# 04_LMS7002M_Misc.net
KiCad netlist of a schematic drawn in Altium Designer
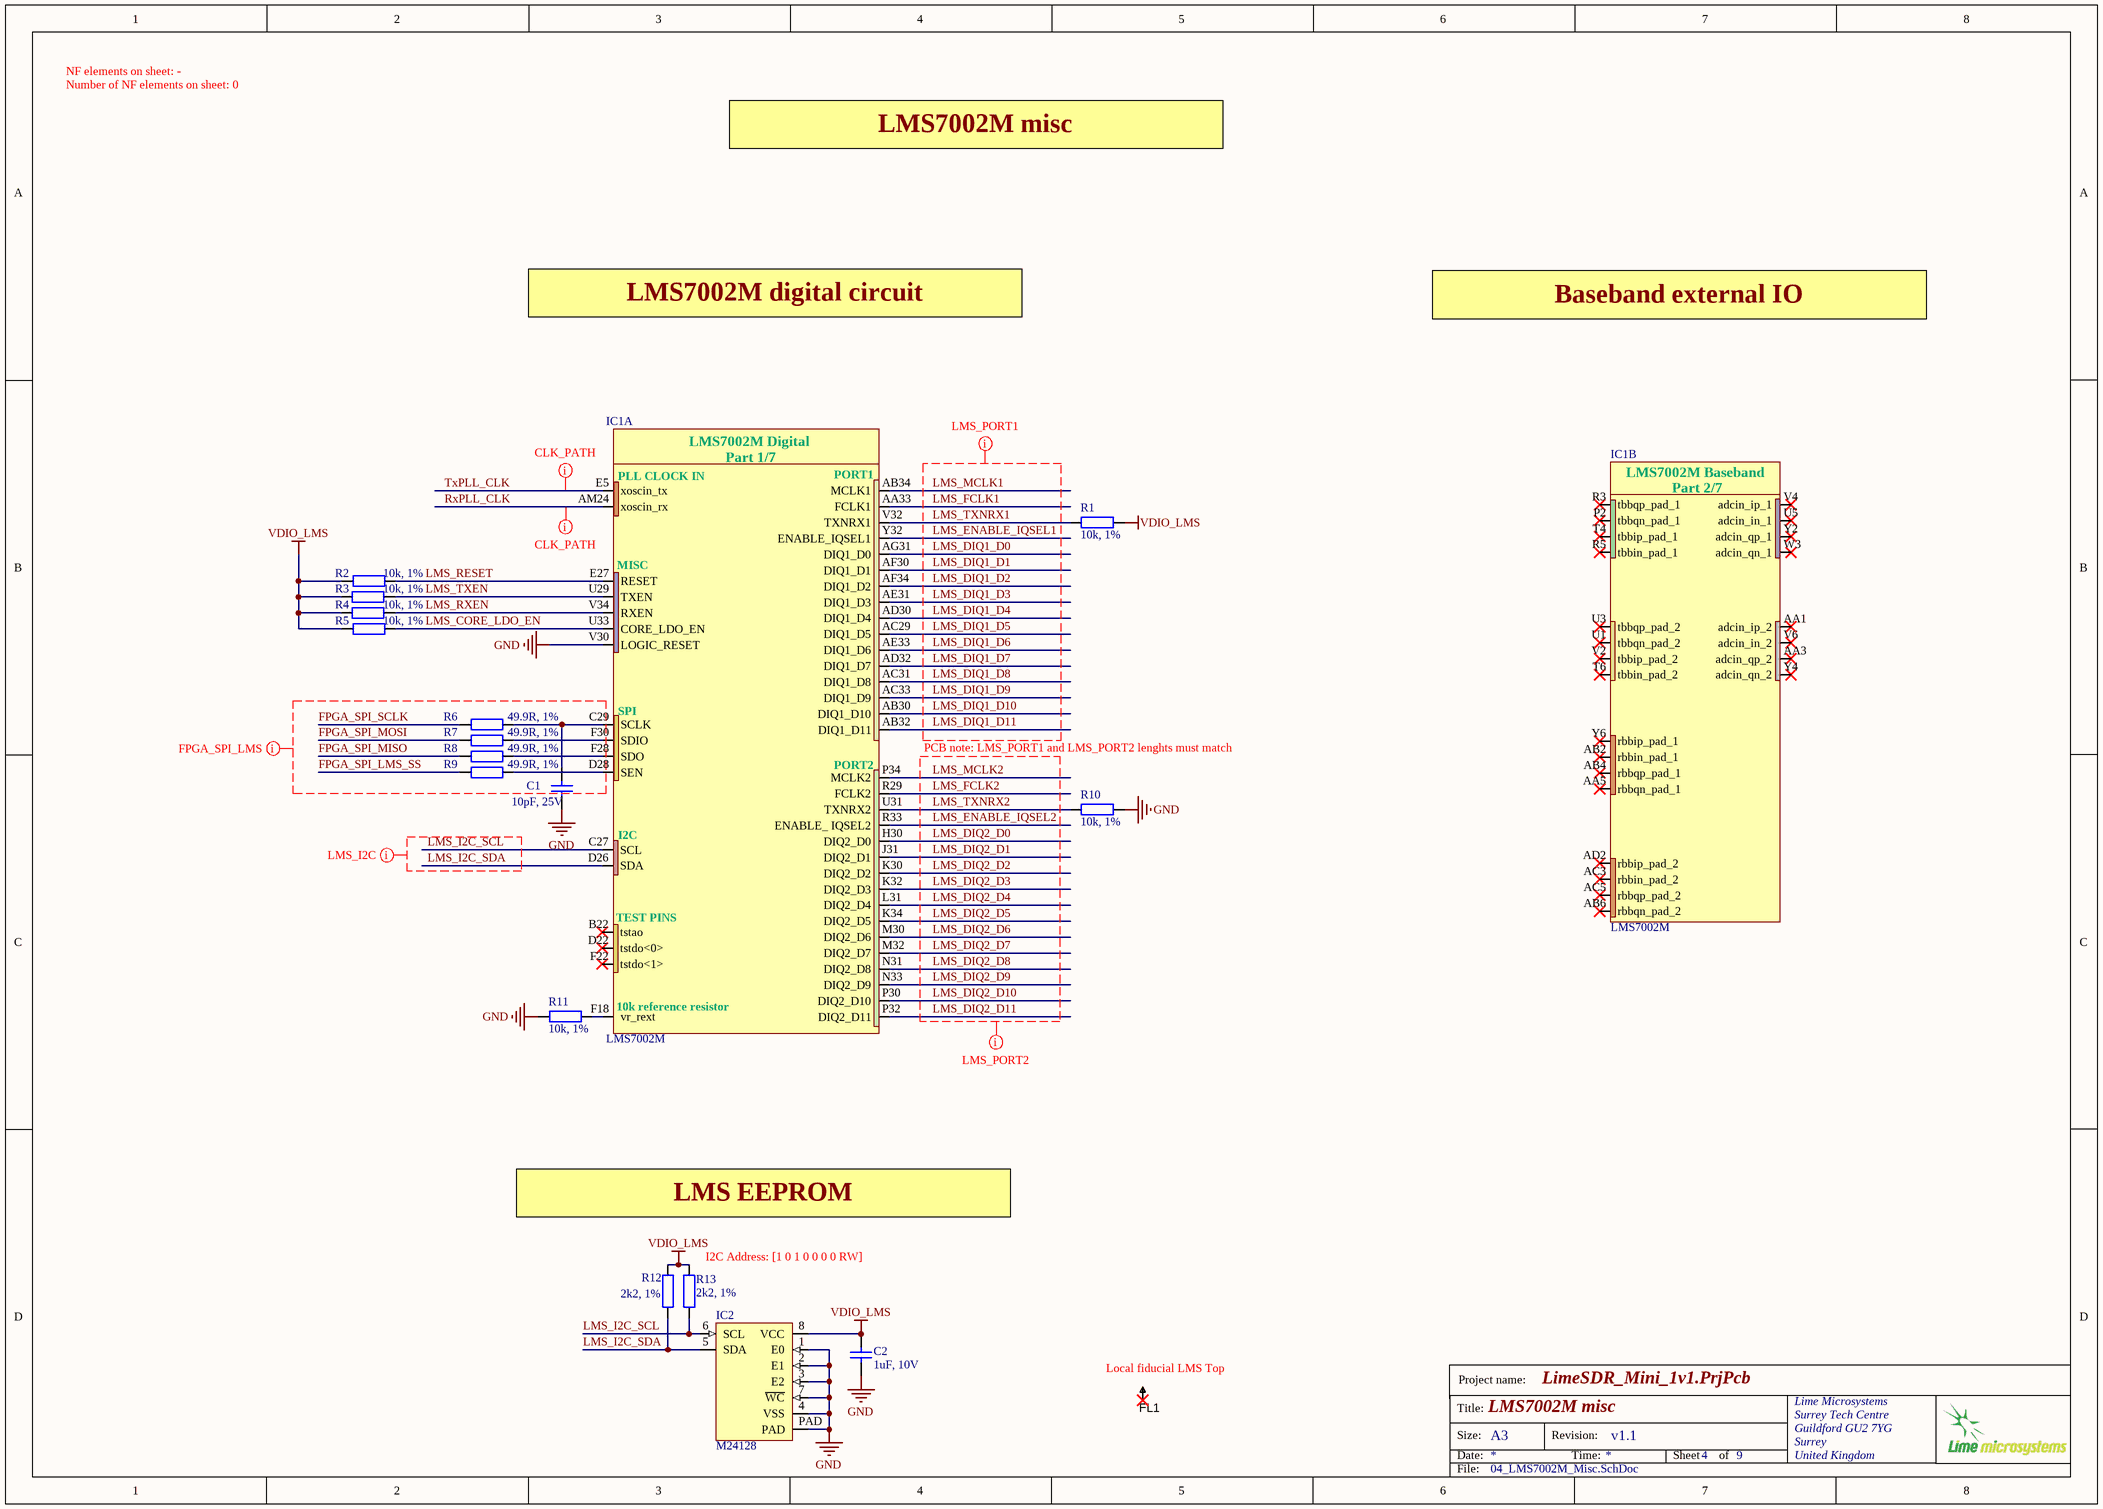
[diagram p0: 04_LMS7002M_Misc.SchDoc]

(export (version "E")
  (design (tool "Eeschema 10.0.6"))
  (components
    (comp (ref "C1")
      (value "10pF, 25V")
      (footprint "CAP0402")
      (fields (field (name "MANUFACTURER") "AVX"))
      (libsource (lib "LimeMicroAltiumLib_schLib") (part "Cap_0402"))
    )
    (comp (ref "C2")
      (value "1uF, 10V")
      (footprint "CAP0402")
      (fields (field (name "MANUFACTURER") "TDK"))
      (libsource (lib "LimeMicroAltiumLib_schLib") (part "Cap_0402"))
    )
    (comp (ref "FL1")
      (value "Fiducial")
      (footprint "Fiducial_local")
      (libsource (lib "VGTU_Altium_lib") (part "Fiducial"))
    )
    (comp (ref "IC1")
      (value "LMS7002M")
      (footprint "LMS7002M_v5_1")
      (description "Schematic symbol revision 3. Default footprint - 0.31mm pad")
      (fields (field (name "MANUFACTURER") "Lime Microsystems"))
      (libsource (lib "LimeMicroAltiumLib_schLib") (part "LMS7002Mr3"))
    )
    (comp (ref "IC2")
      (value "M24128")
      (footprint "M24128-DFMC6TG")
      (fields (field (name "MANUFACTURER") "STMicroelectronics"))
      (libsource (lib "LimeMicroAltiumLib_schLib") (part "M24128-DFMC6TG"))
    )
    (comp (ref "R1")
      (value "10k, 1%")
      (footprint "RES0402")
      (fields (field (name "MANUFACTURER") "Yageo") (field (name "TOLERANCE") "±1%"))
      (libsource (lib "LimeMicroAltiumLib_schLib") (part "Res_0402"))
    )
    (comp (ref "R2")
      (value "10k, 1%")
      (footprint "RES0402")
      (fields (field (name "MANUFACTURER") "Yageo") (field (name "TOLERANCE") "±1%"))
      (libsource (lib "LimeMicroAltiumLib_schLib") (part "Res_0402"))
    )
    (comp (ref "R3")
      (value "10k, 1%")
      (footprint "RES0402")
      (fields (field (name "MANUFACTURER") "Yageo") (field (name "TOLERANCE") "±1%"))
      (libsource (lib "LimeMicroAltiumLib_schLib") (part "Res_0402"))
    )
    (comp (ref "R4")
      (value "10k, 1%")
      (footprint "RES0402")
      (fields (field (name "MANUFACTURER") "Yageo") (field (name "TOLERANCE") "±1%"))
      (libsource (lib "LimeMicroAltiumLib_schLib") (part "Res_0402"))
    )
    (comp (ref "R5")
      (value "10k, 1%")
      (footprint "RES0402")
      (fields (field (name "MANUFACTURER") "Yageo") (field (name "TOLERANCE") "±1%"))
      (libsource (lib "LimeMicroAltiumLib_schLib") (part "Res_0402"))
    )
    (comp (ref "R6")
      (value "49.9R, 1%")
      (footprint "RES0402")
      (fields
        (field (name "TOLERANCE") "±1%")
        (field (name "MANUFACTURER") "Samsung Electro-Mechanics America, Inc.")
        (field (name "MANUFACTURER PART NUMBER") "RC1005F49R9CS")
      )
      (libsource (lib "LimeMicroAltiumLib_schLib") (part "Res_0402"))
    )
    (comp (ref "R7")
      (value "49.9R, 1%")
      (footprint "RES0402")
      (fields
        (field (name "TOLERANCE") "±1%")
        (field (name "MANUFACTURER") "Samsung Electro-Mechanics America, Inc.")
        (field (name "MANUFACTURER PART NUMBER") "RC1005F49R9CS")
      )
      (libsource (lib "LimeMicroAltiumLib_schLib") (part "Res_0402"))
    )
    (comp (ref "R8")
      (value "49.9R, 1%")
      (footprint "RES0402")
      (fields
        (field (name "TOLERANCE") "±1%")
        (field (name "MANUFACTURER") "Samsung Electro-Mechanics America, Inc.")
        (field (name "MANUFACTURER PART NUMBER") "RC1005F49R9CS")
      )
      (libsource (lib "LimeMicroAltiumLib_schLib") (part "Res_0402"))
    )
    (comp (ref "R9")
      (value "49.9R, 1%")
      (footprint "RES0402")
      (fields
        (field (name "TOLERANCE") "±1%")
        (field (name "MANUFACTURER") "Samsung Electro-Mechanics America, Inc.")
        (field (name "MANUFACTURER PART NUMBER") "RC1005F49R9CS")
      )
      (libsource (lib "LimeMicroAltiumLib_schLib") (part "Res_0402"))
    )
    (comp (ref "R10")
      (value "10k, 1%")
      (footprint "RES0402")
      (fields (field (name "MANUFACTURER") "Yageo") (field (name "TOLERANCE") "±1%"))
      (libsource (lib "LimeMicroAltiumLib_schLib") (part "Res_0402"))
    )
    (comp (ref "R11")
      (value "10k, 1%")
      (footprint "RES0402")
      (fields (field (name "MANUFACTURER") "Yageo") (field (name "TOLERANCE") "±1%"))
      (libsource (lib "LimeMicroAltiumLib_schLib") (part "Res_0402"))
    )
    (comp (ref "R12")
      (value "2k2, 1%")
      (footprint "RES0402")
      (fields (field (name "MANUFACTURER") "Stackpole Electronics Inc") (field (name "TOLERANCE") "±1%"))
      (libsource (lib "LimeMicroAltiumLib_schLib") (part "Res_0402"))
    )
    (comp (ref "R13")
      (value "2k2, 1%")
      (footprint "RES0402")
      (fields (field (name "MANUFACTURER") "Stackpole Electronics Inc") (field (name "TOLERANCE") "±1%"))
      (libsource (lib "LimeMicroAltiumLib_schLib") (part "Res_0402"))
    )
  )
  (nets
    (net (code "1") (name "/FPGA_SPI_LMS_SS") (class "Default")
      (node (ref "R9") (pin "2") (pinfunction "2_2") (pintype "passive"))
    )
    (net (code "2") (name "/FPGA_SPI_MISO") (class "Default")
      (node (ref "R8") (pin "2") (pinfunction "2_2") (pintype "passive"))
    )
    (net (code "3") (name "/FPGA_SPI_MOSI") (class "Default")
      (node (ref "R7") (pin "2") (pinfunction "2_2") (pintype "passive"))
    )
    (net (code "4") (name "/FPGA_SPI_SCLK") (class "Default")
      (node (ref "R6") (pin "2") (pinfunction "2_2") (pintype "passive"))
    )
    (net (code "5") (name "/LMS_CORE_LDO_EN") (class "Default")
      (node (ref "IC1") (pin "U33") (pinfunction "CORE_LDO_EN_U33") (pintype "passive"))
      (node (ref "R5") (pin "1") (pinfunction "1_1") (pintype "passive"))
    )
    (net (code "6") (name "/LMS_DIQ1_D0") (class "Default")
      (node (ref "IC1") (pin "AG31") (pinfunction "DIQ1_D0_AG31") (pintype "passive"))
    )
    (net (code "7") (name "/LMS_DIQ1_D1") (class "Default")
      (node (ref "IC1") (pin "AF30") (pinfunction "DIQ1_D1_AF30") (pintype "passive"))
    )
    (net (code "8") (name "/LMS_DIQ1_D2") (class "Default")
      (node (ref "IC1") (pin "AF34") (pinfunction "DIQ1_D2_AF34") (pintype "passive"))
    )
    (net (code "9") (name "/LMS_DIQ1_D3") (class "Default")
      (node (ref "IC1") (pin "AE31") (pinfunction "DIQ1_D3_AE31") (pintype "passive"))
    )
    (net (code "10") (name "/LMS_DIQ1_D4") (class "Default")
      (node (ref "IC1") (pin "AD30") (pinfunction "DIQ1_D4_AD30") (pintype "passive"))
    )
    (net (code "11") (name "/LMS_DIQ1_D5") (class "Default")
      (node (ref "IC1") (pin "AC29") (pinfunction "DIQ1_D5_AC29") (pintype "passive"))
    )
    (net (code "12") (name "/LMS_DIQ1_D6") (class "Default")
      (node (ref "IC1") (pin "AE33") (pinfunction "DIQ1_D6_AE33") (pintype "passive"))
    )
    (net (code "13") (name "/LMS_DIQ1_D7") (class "Default")
      (node (ref "IC1") (pin "AD32") (pinfunction "DIQ1_D7_AD32") (pintype "passive"))
    )
    (net (code "14") (name "/LMS_DIQ1_D8") (class "Default")
      (node (ref "IC1") (pin "AC31") (pinfunction "DIQ1_D8_AC31") (pintype "passive"))
    )
    (net (code "15") (name "/LMS_DIQ1_D9") (class "Default")
      (node (ref "IC1") (pin "AC33") (pinfunction "DIQ1_D9_AC33") (pintype "passive"))
    )
    (net (code "16") (name "/LMS_DIQ1_D10") (class "Default")
      (node (ref "IC1") (pin "AB30") (pinfunction "DIQ1_D10_AB30") (pintype "passive"))
    )
    (net (code "17") (name "/LMS_DIQ1_D11") (class "Default")
      (node (ref "IC1") (pin "AB32") (pinfunction "DIQ1_D11_AB32") (pintype "passive"))
    )
    (net (code "18") (name "/LMS_DIQ2_D0") (class "Default")
      (node (ref "IC1") (pin "H30") (pinfunction "DIQ2_D0_H30") (pintype "passive"))
    )
    (net (code "19") (name "/LMS_DIQ2_D1") (class "Default")
      (node (ref "IC1") (pin "J31") (pinfunction "DIQ2_D1_J31") (pintype "passive"))
    )
    (net (code "20") (name "/LMS_DIQ2_D2") (class "Default")
      (node (ref "IC1") (pin "K30") (pinfunction "DIQ2_D2_K30") (pintype "passive"))
    )
    (net (code "21") (name "/LMS_DIQ2_D3") (class "Default")
      (node (ref "IC1") (pin "K32") (pinfunction "DIQ2_D3_K32") (pintype "passive"))
    )
    (net (code "22") (name "/LMS_DIQ2_D4") (class "Default")
      (node (ref "IC1") (pin "L31") (pinfunction "DIQ2_D4_L31") (pintype "passive"))
    )
    (net (code "23") (name "/LMS_DIQ2_D5") (class "Default")
      (node (ref "IC1") (pin "K34") (pinfunction "DIQ2_D5_K34") (pintype "passive"))
    )
    (net (code "24") (name "/LMS_DIQ2_D6") (class "Default")
      (node (ref "IC1") (pin "M30") (pinfunction "DIQ2_D6_M30") (pintype "passive"))
    )
    (net (code "25") (name "/LMS_DIQ2_D7") (class "Default")
      (node (ref "IC1") (pin "M32") (pinfunction "DIQ2_D7_M32") (pintype "passive"))
    )
    (net (code "26") (name "/LMS_DIQ2_D8") (class "Default")
      (node (ref "IC1") (pin "N31") (pinfunction "DIQ2_D8_N31") (pintype "passive"))
    )
    (net (code "27") (name "/LMS_DIQ2_D9") (class "Default")
      (node (ref "IC1") (pin "N33") (pinfunction "DIQ2_D9_N33") (pintype "passive"))
    )
    (net (code "28") (name "/LMS_DIQ2_D10") (class "Default")
      (node (ref "IC1") (pin "P30") (pinfunction "DIQ2_D10_P30") (pintype "passive"))
    )
    (net (code "29") (name "/LMS_DIQ2_D11") (class "Default")
      (node (ref "IC1") (pin "P32") (pinfunction "DIQ2_D11_P32") (pintype "passive"))
    )
    (net (code "30") (name "/LMS_ENABLE_IQSEL1") (class "Default")
      (node (ref "IC1") (pin "Y32") (pinfunction "ENABLE_IQSEL1_Y32") (pintype "passive"))
    )
    (net (code "31") (name "/LMS_ENABLE_IQSEL2") (class "Default")
      (node (ref "IC1") (pin "R33") (pinfunction "ENABLE__IQSEL2_R33") (pintype "passive"))
    )
    (net (code "32") (name "/LMS_FCLK1") (class "Default")
      (node (ref "IC1") (pin "AA33") (pinfunction "FCLK1_AA33") (pintype "passive"))
    )
    (net (code "33") (name "/LMS_FCLK2") (class "Default")
      (node (ref "IC1") (pin "R29") (pinfunction "FCLK2_R29") (pintype "passive"))
    )
    (net (code "34") (name "/LMS_I2C_SCL") (class "Default")
      (node (ref "IC1") (pin "C27") (pinfunction "SCL_C27") (pintype "passive"))
      (node (ref "IC2") (pin "6") (pinfunction "SCL_6") (pintype "input"))
      (node (ref "R13") (pin "2") (pinfunction "2_2") (pintype "passive"))
    )
    (net (code "35") (name "/LMS_I2C_SDA") (class "Default")
      (node (ref "IC1") (pin "D26") (pinfunction "SDA_D26") (pintype "passive"))
      (node (ref "IC2") (pin "5") (pinfunction "SDA_5") (pintype "bidirectional"))
      (node (ref "R12") (pin "2") (pinfunction "2_2") (pintype "passive"))
    )
    (net (code "36") (name "/LMS_MCLK1") (class "Default")
      (node (ref "IC1") (pin "AB34") (pinfunction "MCLK1_AB34") (pintype "passive"))
    )
    (net (code "37") (name "/LMS_MCLK2") (class "Default")
      (node (ref "IC1") (pin "P34") (pinfunction "MCLK2_P34") (pintype "passive"))
    )
    (net (code "38") (name "/LMS_RESET") (class "Default")
      (node (ref "IC1") (pin "E27") (pinfunction "RESET_E27") (pintype "passive"))
      (node (ref "R2") (pin "1") (pinfunction "1_1") (pintype "passive"))
    )
    (net (code "39") (name "/LMS_RXEN") (class "Default")
      (node (ref "IC1") (pin "V34") (pinfunction "RXEN_V34") (pintype "passive"))
      (node (ref "R4") (pin "2") (pinfunction "2_2") (pintype "passive"))
    )
    (net (code "40") (name "/LMS_TXEN") (class "Default")
      (node (ref "IC1") (pin "U29") (pinfunction "TXEN_U29") (pintype "passive"))
      (node (ref "R3") (pin "2") (pinfunction "2_2") (pintype "passive"))
    )
    (net (code "41") (name "/LMS_TXNRX1") (class "Default")
      (node (ref "IC1") (pin "V32") (pinfunction "TXNRX1_V32") (pintype "passive"))
      (node (ref "R1") (pin "1") (pinfunction "1_1") (pintype "passive"))
    )
    (net (code "42") (name "/LMS_TXNRX2") (class "Default")
      (node (ref "IC1") (pin "U31") (pinfunction "TXNRX2_U31") (pintype "passive"))
      (node (ref "R10") (pin "1") (pinfunction "1_1") (pintype "passive"))
    )
    (net (code "43") (name "/RxPLL_CLK") (class "Default")
      (node (ref "IC1") (pin "AM24") (pinfunction "xoscin_rx_AM24") (pintype "passive"))
    )
    (net (code "44") (name "/TxPLL_CLK") (class "Default")
      (node (ref "IC1") (pin "E5") (pinfunction "xoscin_tx_E5") (pintype "passive"))
    )
    (net (code "45") (name "GND") (class "Default")
      (node (ref "C1") (pin "2") (pinfunction "2_2") (pintype "passive"))
      (node (ref "C2") (pin "2") (pinfunction "2_2") (pintype "passive"))
      (node (ref "IC1") (pin "V30") (pinfunction "LOGIC_RESET_V30") (pintype "passive"))
      (node (ref "IC2") (pin "1") (pinfunction "E0_1") (pintype "input"))
      (node (ref "IC2") (pin "2") (pinfunction "E1_2") (pintype "input"))
      (node (ref "IC2") (pin "3") (pinfunction "E2_3") (pintype "input"))
      (node (ref "IC2") (pin "4") (pinfunction "VSS_4") (pintype "power_in"))
      (node (ref "IC2") (pin "7") (pinfunction "~{WC}_7") (pintype "input"))
      (node (ref "IC2") (pin "PAD") (pinfunction "PAD_PAD") (pintype "power_in"))
      (node (ref "R10") (pin "2") (pinfunction "2_2") (pintype "passive"))
      (node (ref "R11") (pin "2") (pinfunction "2_2") (pintype "passive"))
    )
    (net (code "46") (name "Net-(IC1A-SCLK)") (class "Default")
      (node (ref "C1") (pin "1") (pinfunction "1_1") (pintype "passive"))
      (node (ref "IC1") (pin "C29") (pinfunction "SCLK_C29") (pintype "passive"))
      (node (ref "R6") (pin "1") (pinfunction "1_1") (pintype "passive"))
    )
    (net (code "47") (name "Net-(IC1A-SDIO)") (class "Default")
      (node (ref "IC1") (pin "F30") (pinfunction "SDIO_F30") (pintype "passive"))
      (node (ref "R7") (pin "1") (pinfunction "1_1") (pintype "passive"))
    )
    (net (code "48") (name "Net-(IC1A-SDO)") (class "Default")
      (node (ref "IC1") (pin "F28") (pinfunction "SDO_F28") (pintype "passive"))
      (node (ref "R8") (pin "1") (pinfunction "1_1") (pintype "passive"))
    )
    (net (code "49") (name "Net-(IC1A-SEN)") (class "Default")
      (node (ref "IC1") (pin "D28") (pinfunction "SEN_D28") (pintype "passive"))
      (node (ref "R9") (pin "1") (pinfunction "1_1") (pintype "passive"))
    )
    (net (code "50") (name "Net-(IC1A-vr_rext)") (class "Default")
      (node (ref "IC1") (pin "F18") (pinfunction "vr_rext_F18") (pintype "passive"))
      (node (ref "R11") (pin "1") (pinfunction "1_1") (pintype "passive"))
    )
    (net (code "51") (name "VDIO_LMS") (class "Default")
      (node (ref "C2") (pin "1") (pinfunction "1_1") (pintype "passive"))
      (node (ref "IC2") (pin "8") (pinfunction "VCC_8") (pintype "power_in"))
      (node (ref "R1") (pin "2") (pinfunction "2_2") (pintype "passive"))
      (node (ref "R12") (pin "1") (pinfunction "1_1") (pintype "passive"))
      (node (ref "R13") (pin "1") (pinfunction "1_1") (pintype "passive"))
      (node (ref "R2") (pin "2") (pinfunction "2_2") (pintype "passive"))
      (node (ref "R3") (pin "1") (pinfunction "1_1") (pintype "passive"))
      (node (ref "R4") (pin "1") (pinfunction "1_1") (pintype "passive"))
      (node (ref "R5") (pin "2") (pinfunction "2_2") (pintype "passive"))
    )
    (net (code "52") (name "unconnected-(FL1-Pad1)") (class "Default")
      (node (ref "FL1") (pin "1") (pintype "passive+no_connect"))
    )
    (net (code "53") (name "unconnected-(IC1A-tstao-PadB22)") (class "Default")
      (node (ref "IC1") (pin "B22") (pinfunction "tstao_B22") (pintype "passive+no_connect"))
    )
    (net (code "54") (name "unconnected-(IC1A-tstdo<0>-PadD22)") (class "Default")
      (node (ref "IC1") (pin "D22") (pinfunction "tstdo<0>_D22") (pintype "passive+no_connect"))
    )
    (net (code "55") (name "unconnected-(IC1A-tstdo<1>-PadF22)") (class "Default")
      (node (ref "IC1") (pin "F22") (pinfunction "tstdo<1>_F22") (pintype "passive+no_connect"))
    )
    (net (code "56") (name "unconnected-(IC1B-adcin_in_1-PadU5)") (class "Default")
      (node (ref "IC1") (pin "U5") (pinfunction "adcin_in_1_U5") (pintype "passive+no_connect"))
    )
    (net (code "57") (name "unconnected-(IC1B-adcin_in_2-PadV6)") (class "Default")
      (node (ref "IC1") (pin "V6") (pinfunction "adcin_in_2_V6") (pintype "passive+no_connect"))
    )
    (net (code "58") (name "unconnected-(IC1B-adcin_ip_1-PadV4)") (class "Default")
      (node (ref "IC1") (pin "V4") (pinfunction "adcin_ip_1_V4") (pintype "passive+no_connect"))
    )
    (net (code "59") (name "unconnected-(IC1B-adcin_ip_2-PadAA1)") (class "Default")
      (node (ref "IC1") (pin "AA1") (pinfunction "adcin_ip_2_AA1") (pintype "passive+no_connect"))
    )
    (net (code "60") (name "unconnected-(IC1B-adcin_qn_1-PadW3)") (class "Default")
      (node (ref "IC1") (pin "W3") (pinfunction "adcin_qn_1_W3") (pintype "passive+no_connect"))
    )
    (net (code "61") (name "unconnected-(IC1B-adcin_qn_2-PadY4)") (class "Default")
      (node (ref "IC1") (pin "Y4") (pinfunction "adcin_qn_2_Y4") (pintype "passive+no_connect"))
    )
    (net (code "62") (name "unconnected-(IC1B-adcin_qp_1-PadY2)") (class "Default")
      (node (ref "IC1") (pin "Y2") (pinfunction "adcin_qp_1_Y2") (pintype "passive+no_connect"))
    )
    (net (code "63") (name "unconnected-(IC1B-adcin_qp_2-PadAA3)") (class "Default")
      (node (ref "IC1") (pin "AA3") (pinfunction "adcin_qp_2_AA3") (pintype "passive+no_connect"))
    )
    (net (code "64") (name "unconnected-(IC1B-rbbin_pad_1-PadAB2)") (class "Default")
      (node (ref "IC1") (pin "AB2") (pinfunction "rbbin_pad_1_AB2") (pintype "passive+no_connect"))
    )
    (net (code "65") (name "unconnected-(IC1B-rbbin_pad_2-PadAC3)") (class "Default")
      (node (ref "IC1") (pin "AC3") (pinfunction "rbbin_pad_2_AC3") (pintype "passive+no_connect"))
    )
    (net (code "66") (name "unconnected-(IC1B-rbbip_pad_1-PadY6)") (class "Default")
      (node (ref "IC1") (pin "Y6") (pinfunction "rbbip_pad_1_Y6") (pintype "passive+no_connect"))
    )
    (net (code "67") (name "unconnected-(IC1B-rbbip_pad_2-PadAD2)") (class "Default")
      (node (ref "IC1") (pin "AD2") (pinfunction "rbbip_pad_2_AD2") (pintype "passive+no_connect"))
    )
    (net (code "68") (name "unconnected-(IC1B-rbbqn_pad_1-PadAA5)") (class "Default")
      (node (ref "IC1") (pin "AA5") (pinfunction "rbbqn_pad_1_AA5") (pintype "passive+no_connect"))
    )
    (net (code "69") (name "unconnected-(IC1B-rbbqn_pad_2-PadAB6)") (class "Default")
      (node (ref "IC1") (pin "AB6") (pinfunction "rbbqn_pad_2_AB6") (pintype "passive+no_connect"))
    )
    (net (code "70") (name "unconnected-(IC1B-rbbqp_pad_1-PadAB4)") (class "Default")
      (node (ref "IC1") (pin "AB4") (pinfunction "rbbqp_pad_1_AB4") (pintype "passive+no_connect"))
    )
    (net (code "71") (name "unconnected-(IC1B-rbbqp_pad_2-PadAC5)") (class "Default")
      (node (ref "IC1") (pin "AC5") (pinfunction "rbbqp_pad_2_AC5") (pintype "passive+no_connect"))
    )
    (net (code "72") (name "unconnected-(IC1B-tbbin_pad_1-PadR5)") (class "Default")
      (node (ref "IC1") (pin "R5") (pinfunction "tbbin_pad_1_R5") (pintype "passive+no_connect"))
    )
    (net (code "73") (name "unconnected-(IC1B-tbbin_pad_2-PadT6)") (class "Default")
      (node (ref "IC1") (pin "T6") (pinfunction "tbbin_pad_2_T6") (pintype "passive+no_connect"))
    )
    (net (code "74") (name "unconnected-(IC1B-tbbip_pad_1-PadT4)") (class "Default")
      (node (ref "IC1") (pin "T4") (pinfunction "tbbip_pad_1_T4") (pintype "passive+no_connect"))
    )
    (net (code "75") (name "unconnected-(IC1B-tbbip_pad_2-PadV2)") (class "Default")
      (node (ref "IC1") (pin "V2") (pinfunction "tbbip_pad_2_V2") (pintype "passive+no_connect"))
    )
    (net (code "76") (name "unconnected-(IC1B-tbbqn_pad_1-PadP2)") (class "Default")
      (node (ref "IC1") (pin "P2") (pinfunction "tbbqn_pad_1_P2") (pintype "passive+no_connect"))
    )
    (net (code "77") (name "unconnected-(IC1B-tbbqn_pad_2-PadU1)") (class "Default")
      (node (ref "IC1") (pin "U1") (pinfunction "tbbqn_pad_2_U1") (pintype "passive+no_connect"))
    )
    (net (code "78") (name "unconnected-(IC1B-tbbqp_pad_1-PadR3)") (class "Default")
      (node (ref "IC1") (pin "R3") (pinfunction "tbbqp_pad_1_R3") (pintype "passive+no_connect"))
    )
    (net (code "79") (name "unconnected-(IC1B-tbbqp_pad_2-PadU3)") (class "Default")
      (node (ref "IC1") (pin "U3") (pinfunction "tbbqp_pad_2_U3") (pintype "passive+no_connect"))
    )
  )
)
